# 11_5V_RAIL_ADC.net
KiCad netlist of a schematic drawn in Altium Designer
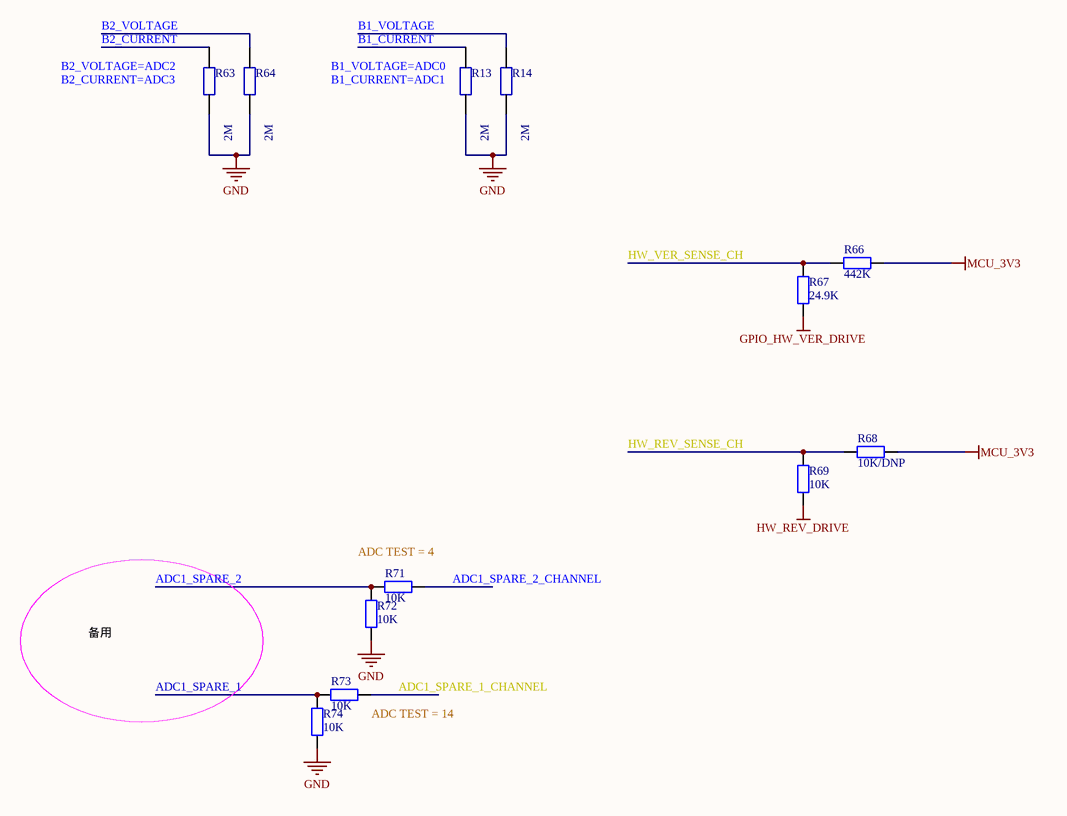
[diagram p0: 11_5V_RAIL_ADC.SchDoc]

(export (version "E")
  (design (tool "Eeschema 10.0.6"))
  (components
    (comp (ref "R13")
      (value "2M")
      (footprint "0402R")
      (description "0402R10K 1%")
      (libsource (lib "CUAV") (part "0402R10K"))
    )
    (comp (ref "R14")
      (value "2M")
      (footprint "0402R")
      (description "0402R10K 1%")
      (libsource (lib "CUAV") (part "0402R10K"))
    )
    (comp (ref "R63")
      (value "2M")
      (footprint "0402R")
      (description "0402R10K 1%")
      (libsource (lib "CUAV") (part "0402R10K"))
    )
    (comp (ref "R64")
      (value "2M")
      (footprint "0402R")
      (description "0402R10K 1%")
      (libsource (lib "CUAV") (part "0402R10K"))
    )
    (comp (ref "R66")
      (value "442K")
      (description "Resistor")
      (fields (field (name "PUBLISHER") "Altium Limited"))
      (libsource (lib "Miscellaneous Devices") (part "Res2"))
    )
    (comp (ref "R67")
      (value "24.9K")
      (description "Resistor")
      (fields (field (name "PUBLISHER") "Altium Limited"))
      (libsource (lib "") (part "Res2_1"))
    )
    (comp (ref "R68")
      (value "10K/DNP")
      (description "Resistor")
      (fields (field (name "PUBLISHER") "Altium Limited"))
      (libsource (lib "Miscellaneous Devices") (part "Res2"))
    )
    (comp (ref "R69")
      (value "10K")
      (description "Resistor")
      (fields (field (name "PUBLISHER") "Altium Limited"))
      (libsource (lib "") (part "Res2_1"))
    )
    (comp (ref "R71")
      (value "10K")
      (description "Resistor")
      (fields (field (name "PUBLISHER") "Altium Limited"))
      (libsource (lib "Miscellaneous Devices") (part "Res2"))
    )
    (comp (ref "R72")
      (value "10K")
      (description "Resistor")
      (fields (field (name "PUBLISHER") "Altium Limited"))
      (libsource (lib "") (part "Res2_1"))
    )
    (comp (ref "R73")
      (value "10K")
      (description "Resistor")
      (fields (field (name "PUBLISHER") "Altium Limited"))
      (libsource (lib "Miscellaneous Devices") (part "Res2"))
    )
    (comp (ref "R74")
      (value "10K")
      (description "Resistor")
      (fields (field (name "PUBLISHER") "Altium Limited"))
      (libsource (lib "") (part "Res2_1"))
    )
  )
  (nets
    (net (code "3") (name "/ADC1_SPARE_1") (class "Default")
      (node (ref "R73") (pin "1") (pinfunction "1_1") (pintype "passive"))
      (node (ref "R74") (pin "2") (pinfunction "2_2") (pintype "passive"))
    )
    (net (code "4") (name "/ADC1_SPARE_1_CHANNEL") (class "Default")
      (node (ref "R73") (pin "2") (pinfunction "2_2") (pintype "passive"))
    )
    (net (code "5") (name "/ADC1_SPARE_2") (class "Default")
      (node (ref "R71") (pin "1") (pinfunction "1_1") (pintype "passive"))
      (node (ref "R72") (pin "2") (pinfunction "2_2") (pintype "passive"))
    )
    (net (code "6") (name "/ADC1_SPARE_2_CHANNEL") (class "Default")
      (node (ref "R71") (pin "2") (pinfunction "2_2") (pintype "passive"))
    )
    (net (code "7") (name "/B1_CURRENT") (class "Default") (node (ref "R13") (pin "1") (pintype "passive")))
    (net (code "9") (name "/B1_VOLTAGE") (class "Default") (node (ref "R14") (pin "1") (pintype "passive")))
    (net (code "11") (name "/B2_CURRENT") (class "Default") (node (ref "R63") (pin "1") (pintype "passive")))
    (net (code "13") (name "/B2_VOLTAGE") (class "Default") (node (ref "R64") (pin "1") (pintype "passive")))
    (net (code "15") (name "/HW_REV_SENSE_CH") (class "Default")
      (node (ref "R68") (pin "1") (pinfunction "1_1") (pintype "passive"))
      (node (ref "R69") (pin "2") (pinfunction "2_2") (pintype "passive"))
    )
    (net (code "16") (name "/HW_VER_SENSE_CH") (class "Default")
      (node (ref "R66") (pin "1") (pinfunction "1_1") (pintype "passive"))
      (node (ref "R67") (pin "2") (pinfunction "2_2") (pintype "passive"))
    )
    (net (code "18") (name "GND") (class "Default")
      (node (ref "R13") (pin "2") (pintype "passive"))
      (node (ref "R14") (pin "2") (pintype "passive"))
      (node (ref "R63") (pin "2") (pintype "passive"))
      (node (ref "R64") (pin "2") (pintype "passive"))
      (node (ref "R72") (pin "1") (pinfunction "1_1") (pintype "passive"))
      (node (ref "R74") (pin "1") (pinfunction "1_1") (pintype "passive"))
    )
    (net (code "19") (name "GPIO_HW_VER_DRIVE") (class "Default")
      (node (ref "R67") (pin "1") (pinfunction "1_1") (pintype "passive"))
    )
    (net (code "20") (name "HW_REV_DRIVE") (class "Default")
      (node (ref "R69") (pin "1") (pinfunction "1_1") (pintype "passive"))
    )
    (net (code "21") (name "MCU_3V3") (class "Default")
      (node (ref "R66") (pin "2") (pinfunction "2_2") (pintype "passive"))
      (node (ref "R68") (pin "2") (pinfunction "2_2") (pintype "passive"))
    )
  )
)
